# WL_430.net
KiCad netlist of a schematic drawn in Altium Designer
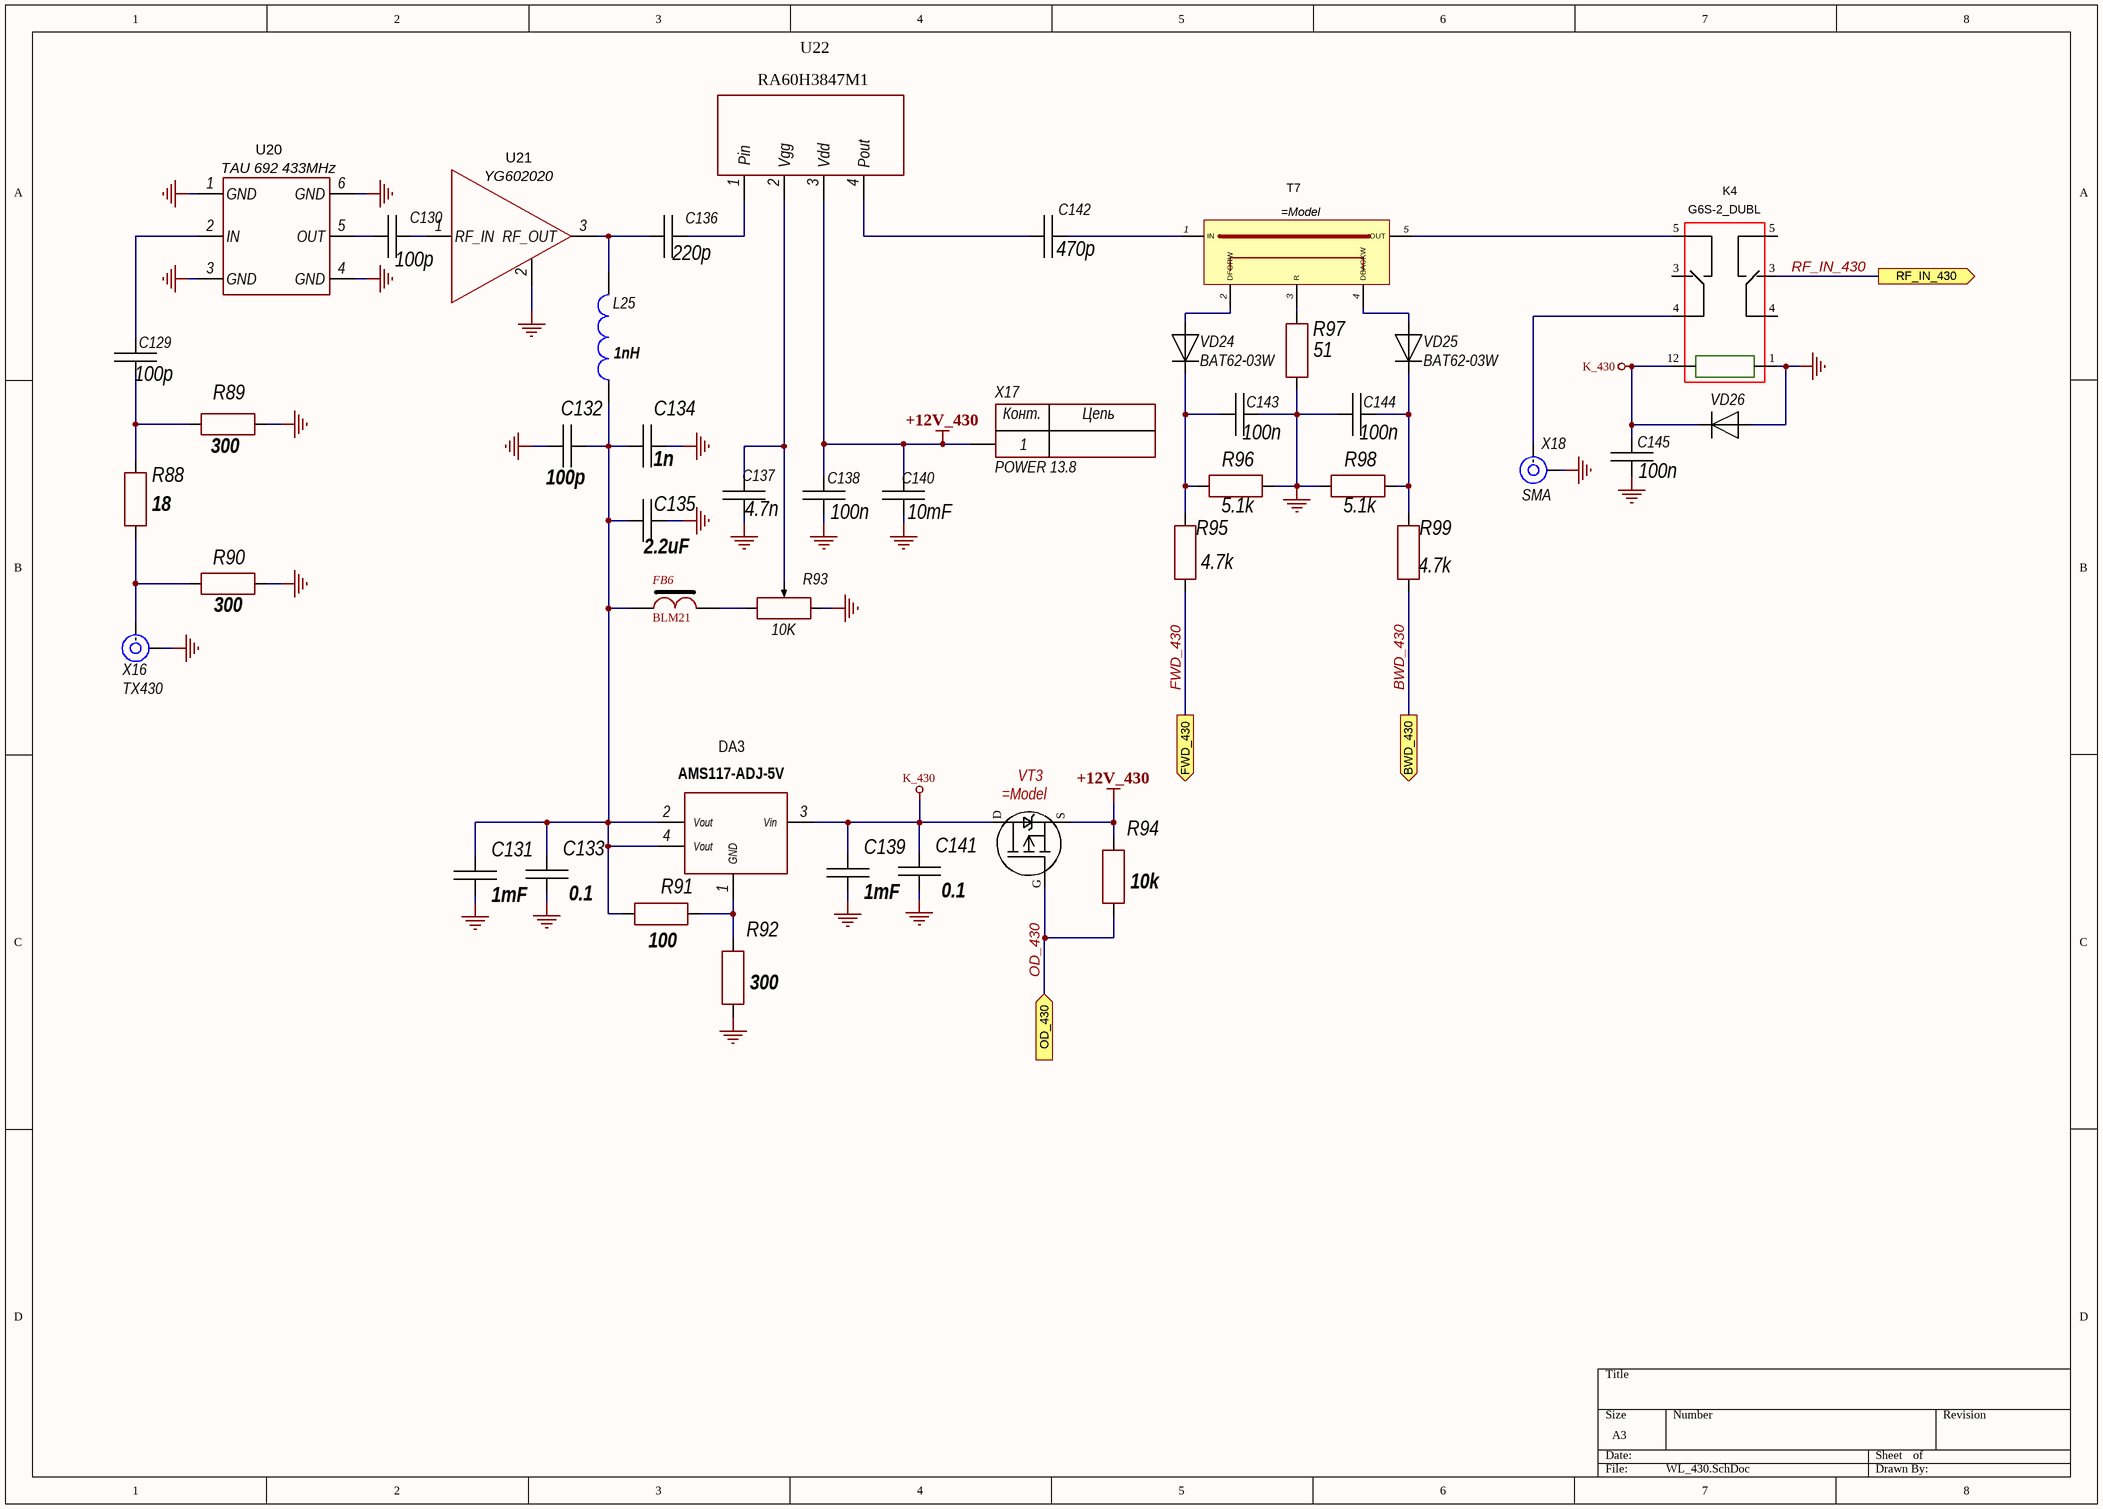
[diagram p0: WL_430.SchDoc]

(export (version "E")
  (design (tool "Eeschema 10.0.6"))
  (components
    (comp (ref "C129")
      (value "100p")
      (footprint "standard:CH0805C")
      (libsource (lib "Discrete") (part "Capacitor"))
    )
    (comp (ref "C130")
      (value "100p")
      (footprint "standard:CH0805C")
      (libsource (lib "Discrete") (part "Capacitor"))
    )
    (comp (ref "C131")
      (value "1mF")
      (footprint "standard:CH0805C")
      (libsource (lib "Discrete") (part "Capacitor"))
    )
    (comp (ref "C132")
      (value "100p")
      (footprint "standard:CH0805C")
      (libsource (lib "Discrete") (part "Capacitor"))
    )
    (comp (ref "C133")
      (value "0.1")
      (footprint "standard:CH0805C")
      (libsource (lib "Discrete") (part "Capacitor"))
    )
    (comp (ref "C134")
      (value "1n")
      (footprint "standard:CH0805C")
      (libsource (lib "Discrete") (part "Capacitor"))
    )
    (comp (ref "C135")
      (value "2.2uF")
      (footprint "standard:CH0805C")
      (libsource (lib "Discrete") (part "Capacitor"))
    )
    (comp (ref "C136")
      (value "220p")
      (footprint "standard:CH0805C")
      (libsource (lib "Discrete") (part "Capacitor"))
    )
    (comp (ref "C137")
      (value "4.7n")
      (footprint "standard:CH0805C")
      (libsource (lib "Discrete") (part "Capacitor"))
    )
    (comp (ref "C138")
      (value "100n")
      (footprint "standard:CH1206C")
      (libsource (lib "Discrete") (part "Capacitor"))
    )
    (comp (ref "C139")
      (value "1mF")
      (footprint "standard:CH0805C")
      (libsource (lib "Discrete") (part "Capacitor"))
    )
    (comp (ref "C140")
      (value "10mF")
      (footprint "standard:CH1206C")
      (libsource (lib "Discrete") (part "Capacitor"))
    )
    (comp (ref "C141")
      (value "0.1")
      (footprint "standard:CH0805C")
      (libsource (lib "Discrete") (part "Capacitor"))
    )
    (comp (ref "C142")
      (value "470p")
      (footprint "standard:CH1210C")
      (libsource (lib "Discrete") (part "Capacitor"))
    )
    (comp (ref "C143")
      (value "100n")
      (footprint "standard:CH0805C")
      (libsource (lib "Discrete") (part "Capacitor"))
    )
    (comp (ref "C144")
      (value "100n")
      (footprint "standard:CH0805C")
      (libsource (lib "Discrete") (part "Capacitor"))
    )
    (comp (ref "C145")
      (value "100n")
      (footprint "standard:CH0805C")
      (libsource (lib "") (part "Capacitor_1"))
    )
    (comp (ref "DA3") (value "AMS117-ADJ-5V") (footprint "SOT223") (libsource (lib "Analog") (part "AMS117")))
    (comp (ref "FB6") (value "BLM21") (footprint "CH0805L") (libsource (lib "Discrete") (part "FB-1")))
    (comp (ref "K4")
      (value "G6S-2_DUBL")
      (footprint "G6S-2_DUBL")
      (libsource (lib "Relay") (part "G6S-2_DUBL"))
    )
    (comp (ref "L25")
      (value "1nH")
      (footprint "katuhka")
      (libsource (lib "Transformers") (part "Inductor ring"))
    )
    (comp (ref "R88") (value "18") (footprint "standard:CH0805R") (libsource (lib "") (part "Resistor_2")))
    (comp (ref "R89")
      (value "300")
      (footprint "standard:CH0805R")
      (libsource (lib "Discrete") (part "Resistor"))
    )
    (comp (ref "R90")
      (value "300")
      (footprint "standard:CH0805R")
      (libsource (lib "Discrete") (part "Resistor"))
    )
    (comp (ref "R91")
      (value "100")
      (footprint "standard:CH0805R")
      (libsource (lib "Discrete") (part "Resistor"))
    )
    (comp (ref "R92") (value "300") (footprint "standard:CH0805R") (libsource (lib "") (part "Resistor_1")))
    (comp (ref "R93")
      (value "10K")
      (footprint "custom:RES: 3296W")
      (libsource (lib "Discrete") (part "ADJ resistor"))
    )
    (comp (ref "R94") (value "10k") (footprint "standard:CH0805R") (libsource (lib "") (part "Resistor_1")))
    (comp (ref "R95") (value "4.7k") (footprint "standard:CH0805R") (libsource (lib "") (part "Resistor_2")))
    (comp (ref "R96")
      (value "5.1k")
      (footprint "standard:CH0805R")
      (libsource (lib "Discrete") (part "Resistor"))
    )
    (comp (ref "R97") (value "51") (footprint "standard:CH1206R") (libsource (lib "") (part "Resistor_1")))
    (comp (ref "R98")
      (value "5.1k")
      (footprint "standard:CH0805R")
      (libsource (lib "Discrete") (part "Resistor"))
    )
    (comp (ref "R99") (value "4.7k") (footprint "standard:CH0805R") (libsource (lib "") (part "Resistor_2")))
    (comp (ref "T7") (value "~") (footprint "SWR_D") (libsource (lib "Transformers") (part "VHF_KSV1")))
    (comp (ref "U20")
      (value "TAU 692 433MHz")
      (footprint "TAU692")
      (libsource (lib "Digital") (part "TAU692"))
    )
    (comp (ref "U21")
      (value "YG602020")
      (footprint "SOT89_123")
      (libsource (lib "Digital") (part "YG602020"))
    )
    (comp (ref "U22")
      (value "RA60H3847M1")
      (footprint "RA80H1415M1 - duplicate")
      (libsource (lib "Digital") (part "RA80H1415M1"))
    )
    (comp (ref "VD24") (value "BAT62-03W") (footprint "1N4148") (libsource (lib "Diods") (part "Diod")))
    (comp (ref "VD25") (value "BAT62-03W") (footprint "1N4148") (libsource (lib "Diods") (part "Diod")))
    (comp (ref "VD26") (value "~") (footprint "1N4148") (libsource (lib "Diods") (part "Diod")))
    (comp (ref "VT3") (value "~") (footprint "SOT23_132") (libsource (lib "Transistor") (part "P-KANAL")))
    (comp (ref "X16")
      (value "TX430")
      (footprint "CON: u.Fl")
      (description "RF")
      (libsource (lib "Connectors") (part "SMA"))
    )
    (comp (ref "X17")
      (value "POWER 13.8")
      (footprint "CON: KNIFE_5MM")
      (libsource (lib "Connectors") (part "1-Connector"))
    )
    (comp (ref "X18")
      (value "SMA")
      (footprint "custom:CON: SMA")
      (description "RF")
      (libsource (lib "Connectors") (part "SMA"))
    )
  )
  (nets
    (net (code "1") (name "+12V_430") (class "Default")
      (node (ref "C138") (pin "2") (pinfunction "2_2") (pintype "power_in"))
      (node (ref "C140") (pin "2") (pinfunction "2_2") (pintype "power_in"))
      (node (ref "R94") (pin "2") (pinfunction "2_2") (pintype "passive"))
      (node (ref "U22") (pin "3") (pinfunction "Vdd_3") (pintype "passive"))
      (node (ref "VT3") (pin "2") (pinfunction "Исток_2") (pintype "passive"))
      (node (ref "X17") (pin "1") (pinfunction "1_1") (pintype "passive"))
    )
    (net (code "2") (name "/BWD_430") (class "Default")
      (node (ref "R99") (pin "2") (pinfunction "2_2") (pintype "passive"))
    )
    (net (code "3") (name "/FWD_430") (class "Default")
      (node (ref "R95") (pin "2") (pinfunction "2_2") (pintype "passive"))
    )
    (net (code "4") (name "/OD_430") (class "Default")
      (node (ref "R94") (pin "1") (pinfunction "1_1") (pintype "passive"))
      (node (ref "VT3") (pin "1") (pinfunction "Затвор(Gate)_1") (pintype "passive"))
    )
    (net (code "5") (name "/RF_IN_430") (class "Default")
      (node (ref "K4") (pin "3") (pinfunction "3_3") (pintype "passive"))
    )
    (net (code "6") (name "GND") (class "Default")
      (node (ref "C131") (pin "1") (pinfunction "1_1") (pintype "power_in"))
      (node (ref "C132") (pin "2") (pinfunction "2_2") (pintype "power_in"))
      (node (ref "C133") (pin "1") (pinfunction "1_1") (pintype "power_in"))
      (node (ref "C134") (pin "2") (pinfunction "2_2") (pintype "power_in"))
      (node (ref "C135") (pin "2") (pinfunction "2_2") (pintype "power_in"))
      (node (ref "C137") (pin "1") (pinfunction "1_1") (pintype "power_in"))
      (node (ref "C138") (pin "1") (pinfunction "1_1") (pintype "power_in"))
      (node (ref "C139") (pin "1") (pinfunction "1_1") (pintype "power_in"))
      (node (ref "C140") (pin "1") (pinfunction "1_1") (pintype "power_in"))
      (node (ref "C141") (pin "1") (pinfunction "1_1") (pintype "power_in"))
      (node (ref "C143") (pin "1") (pinfunction "1_1") (pintype "power_in"))
      (node (ref "C144") (pin "2") (pinfunction "2_2") (pintype "power_in"))
      (node (ref "C145") (pin "2") (pinfunction "2_2") (pintype "power_in"))
      (node (ref "K4") (pin "1") (pinfunction "1_1") (pintype "passive"))
      (node (ref "R89") (pin "1") (pinfunction "1_1") (pintype "passive"))
      (node (ref "R90") (pin "1") (pinfunction "1_1") (pintype "passive"))
      (node (ref "R92") (pin "1") (pinfunction "1_1") (pintype "passive"))
      (node (ref "R93") (pin "3") (pinfunction "3_3") (pintype "passive"))
      (node (ref "R96") (pin "1") (pinfunction "1_1") (pintype "passive"))
      (node (ref "R97") (pin "1") (pinfunction "1_1") (pintype "passive"))
      (node (ref "R98") (pin "2") (pinfunction "2_2") (pintype "passive"))
      (node (ref "U20") (pin "1") (pinfunction "GND_1") (pintype "passive"))
      (node (ref "U20") (pin "3") (pinfunction "GND_3") (pintype "passive"))
      (node (ref "U20") (pin "4") (pinfunction "GND_4") (pintype "passive"))
      (node (ref "U20") (pin "6") (pinfunction "GND_6") (pintype "passive"))
      (node (ref "U21") (pin "2") (pinfunction "GND_2") (pintype "passive"))
      (node (ref "VD26") (pin "1") (pinfunction "1_1") (pintype "passive"))
      (node (ref "X16") (pin "2") (pinfunction "IN_2") (pintype "passive"))
      (node (ref "X18") (pin "2") (pinfunction "IN_2") (pintype "passive"))
    )
    (net (code "7") (name "K_430") (class "Default")
      (node (ref "C139") (pin "2") (pinfunction "2_2") (pintype "power_in"))
      (node (ref "C141") (pin "2") (pinfunction "2_2") (pintype "power_in"))
      (node (ref "C145") (pin "1") (pinfunction "1_1") (pintype "power_in"))
      (node (ref "DA3") (pin "3") (pinfunction "Vin_3") (pintype "passive"))
      (node (ref "K4") (pin "12") (pinfunction "12_12") (pintype "passive"))
      (node (ref "VD26") (pin "2") (pinfunction "2_2") (pintype "passive"))
      (node (ref "VT3") (pin "3") (pinfunction "Сток_3") (pintype "passive"))
    )
    (net (code "8") (name "Net-(C129-Pad2)") (class "Default")
      (node (ref "C129") (pin "2") (pinfunction "2_2") (pintype "power_in"))
      (node (ref "R88") (pin "1") (pinfunction "1_1") (pintype "passive"))
      (node (ref "R89") (pin "2") (pinfunction "2_2") (pintype "passive"))
    )
    (net (code "9") (name "Net-(C131-Pad2)") (class "Default")
      (node (ref "C131") (pin "2") (pinfunction "2_2") (pintype "power_in"))
      (node (ref "C132") (pin "1") (pinfunction "1_1") (pintype "power_in"))
      (node (ref "C133") (pin "2") (pinfunction "2_2") (pintype "power_in"))
      (node (ref "C134") (pin "1") (pinfunction "1_1") (pintype "power_in"))
      (node (ref "C135") (pin "1") (pinfunction "1_1") (pintype "power_in"))
      (node (ref "DA3") (pin "2") (pinfunction "Vout_2") (pintype "passive"))
      (node (ref "DA3") (pin "4") (pinfunction "Vout_4") (pintype "passive"))
      (node (ref "FB6") (pin "1") (pinfunction "1_1") (pintype "passive"))
      (node (ref "L25") (pin "2") (pinfunction "2_2") (pintype "passive"))
      (node (ref "R91") (pin "2") (pinfunction "2_2") (pintype "passive"))
    )
    (net (code "10") (name "Net-(C143-Pad2)") (class "Default")
      (node (ref "C143") (pin "2") (pinfunction "2_2") (pintype "power_in"))
      (node (ref "R95") (pin "1") (pinfunction "1_1") (pintype "passive"))
      (node (ref "R96") (pin "2") (pinfunction "2_2") (pintype "passive"))
      (node (ref "VD24") (pin "2") (pinfunction "2_2") (pintype "passive"))
    )
    (net (code "11") (name "Net-(C144-Pad1)") (class "Default")
      (node (ref "C144") (pin "1") (pinfunction "1_1") (pintype "power_in"))
      (node (ref "R98") (pin "1") (pinfunction "1_1") (pintype "passive"))
      (node (ref "R99") (pin "1") (pinfunction "1_1") (pintype "passive"))
      (node (ref "VD25") (pin "2") (pinfunction "2_2") (pintype "passive"))
    )
    (net (code "12") (name "Net-(DA3-GND)") (class "Default")
      (node (ref "DA3") (pin "1") (pinfunction "GND_1") (pintype "passive"))
      (node (ref "R91") (pin "1") (pinfunction "1_1") (pintype "passive"))
      (node (ref "R92") (pin "2") (pinfunction "2_2") (pintype "passive"))
    )
    (net (code "13") (name "Net-(FB6-Pad2)") (class "Default")
      (node (ref "FB6") (pin "2") (pinfunction "2_2") (pintype "passive"))
      (node (ref "R93") (pin "1") (pinfunction "1_1") (pintype "passive"))
    )
    (net (code "14") (name "Net-(K4-Pad4)_1") (class "Default")
      (node (ref "K4") (pin "4") (pinfunction "4_4") (pintype "passive"))
      (node (ref "X18") (pin "1") (pinfunction "IN_1") (pintype "passive"))
    )
    (net (code "15") (name "Net-(R88-Pad2)") (class "Default")
      (node (ref "R88") (pin "2") (pinfunction "2_2") (pintype "passive"))
      (node (ref "R90") (pin "2") (pinfunction "2_2") (pintype "passive"))
      (node (ref "X16") (pin "1") (pinfunction "IN_1") (pintype "passive"))
    )
    (net (code "16") (name "Net-(T7-DBACKW)") (class "Default")
      (node (ref "T7") (pin "4") (pinfunction "DBACKW_4") (pintype "passive"))
      (node (ref "VD25") (pin "1") (pinfunction "1_1") (pintype "passive"))
    )
    (net (code "17") (name "Net-(T7-DFORW)") (class "Default")
      (node (ref "T7") (pin "2") (pinfunction "DFORW_2") (pintype "passive"))
      (node (ref "VD24") (pin "1") (pinfunction "1_1") (pintype "passive"))
    )
    (net (code "18") (name "Net-(T7-IN)") (class "Default")
      (node (ref "C142") (pin "1") (pinfunction "1_1") (pintype "power_in"))
      (node (ref "T7") (pin "1") (pinfunction "IN_1") (pintype "passive"))
    )
    (net (code "19") (name "Net-(T7-OUT)") (class "Default")
      (node (ref "K4") (pin "5") (pinfunction "5_5") (pintype "passive"))
      (node (ref "T7") (pin "5") (pinfunction "OUT_5") (pintype "passive"))
    )
    (net (code "20") (name "Net-(T7-R)") (class "Default")
      (node (ref "R97") (pin "2") (pinfunction "2_2") (pintype "passive"))
      (node (ref "T7") (pin "3") (pinfunction "R_3") (pintype "passive"))
    )
    (net (code "21") (name "Net-(U20-IN)") (class "Default")
      (node (ref "C129") (pin "1") (pinfunction "1_1") (pintype "power_in"))
      (node (ref "U20") (pin "2") (pinfunction "IN_2") (pintype "passive"))
    )
    (net (code "22") (name "Net-(U20-OUT)") (class "Default")
      (node (ref "C130") (pin "2") (pinfunction "2_2") (pintype "power_in"))
      (node (ref "U20") (pin "5") (pinfunction "OUT_5") (pintype "passive"))
    )
    (net (code "23") (name "Net-(U21-RF_IN)") (class "Default")
      (node (ref "C130") (pin "1") (pinfunction "1_1") (pintype "power_in"))
      (node (ref "U21") (pin "1") (pinfunction "RF_IN_1") (pintype "passive"))
    )
    (net (code "24") (name "Net-(U21-RF_OUT)") (class "Default")
      (node (ref "C136") (pin "2") (pinfunction "2_2") (pintype "power_in"))
      (node (ref "L25") (pin "1") (pinfunction "1_1") (pintype "passive"))
      (node (ref "U21") (pin "3") (pinfunction "RF_OUT_3") (pintype "passive"))
    )
    (net (code "25") (name "Net-(U22-Pin)") (class "Default")
      (node (ref "C136") (pin "1") (pinfunction "1_1") (pintype "power_in"))
      (node (ref "U22") (pin "1") (pinfunction "Pin_1") (pintype "passive"))
    )
    (net (code "26") (name "Net-(U22-Pout)") (class "Default")
      (node (ref "C142") (pin "2") (pinfunction "2_2") (pintype "power_in"))
      (node (ref "U22") (pin "4") (pinfunction "Pout_4") (pintype "passive"))
    )
    (net (code "27") (name "Net-(U22-Vgg)") (class "Default")
      (node (ref "C137") (pin "2") (pinfunction "2_2") (pintype "power_in"))
      (node (ref "R93") (pin "2") (pinfunction "2_2") (pintype "passive"))
      (node (ref "U22") (pin "2") (pinfunction "Vgg_2") (pintype "passive"))
    )
    (net (code "28") (name "unconnected-(K4-Pad3)") (class "Default")
      (node (ref "K4") (pin "3") (pinfunction "3_3") (pintype "passive"))
    )
    (net (code "29") (name "unconnected-(K4-Pad4)") (class "Default")
      (node (ref "K4") (pin "4") (pinfunction "4_4") (pintype "passive"))
    )
    (net (code "30") (name "unconnected-(K4-Pad5)") (class "Default")
      (node (ref "K4") (pin "5") (pinfunction "5_5") (pintype "passive"))
    )
  )
)
